# VF_4Channel_ResistanceMixer.net
KiCad netlist of a schematic drawn in EAGLE
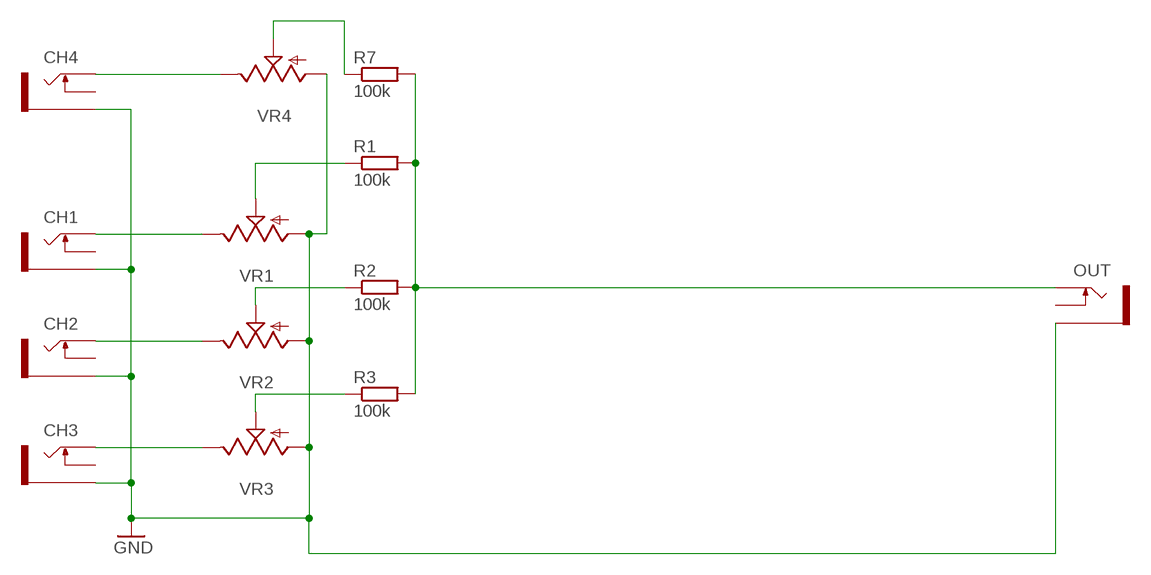
[diagram p0: schematic, sheet 1]

(export (version "E")
  (design (tool "Eeschema 10.0.6"))
  (components
    (comp (ref "CH1")
      (value "THONKICONNNEW")
      (footprint "eagle-import:WQP-PJ301M-12_JACK")
      (libsource (lib "eagle-import") (part "THONKICONNNEW"))
    )
    (comp (ref "CH2")
      (value "THONKICONNNEW")
      (footprint "eagle-import:WQP-PJ301M-12_JACK")
      (libsource (lib "eagle-import") (part "THONKICONNNEW"))
    )
    (comp (ref "CH3")
      (value "THONKICONNNEW")
      (footprint "eagle-import:WQP-PJ301M-12_JACK")
      (libsource (lib "eagle-import") (part "THONKICONNNEW"))
    )
    (comp (ref "CH4")
      (value "THONKICONNNEW")
      (footprint "eagle-import:WQP-PJ301M-12_JACK")
      (libsource (lib "eagle-import") (part "THONKICONNNEW"))
    )
    (comp (ref "OUT")
      (value "THONKICONNNEW")
      (footprint "eagle-import:WQP-PJ301M-12_JACK")
      (libsource (lib "eagle-import") (part "THONKICONNNEW"))
    )
    (comp (ref "R1")
      (value "100k")
      (footprint "eagle-import:7MM_RESISTOR")
      (libsource (lib "eagle-import") (part "RESISTOR7MM"))
    )
    (comp (ref "R2")
      (value "100k")
      (footprint "eagle-import:7MM_RESISTOR")
      (libsource (lib "eagle-import") (part "RESISTOR7MM"))
    )
    (comp (ref "R3")
      (value "100k")
      (footprint "eagle-import:7MM_RESISTOR")
      (libsource (lib "eagle-import") (part "RESISTOR7MM"))
    )
    (comp (ref "R7")
      (value "100k")
      (footprint "eagle-import:7MM_RESISTOR")
      (libsource (lib "eagle-import") (part "RESISTOR7MM"))
    )
    (comp (ref "VR1")
      (value "9MM_SNAP-IN_POT_")
      (footprint "eagle-import:9MM_SNAP-IN_POT")
      (libsource (lib "eagle-import") (part "9MM_SNAP-IN_POT_"))
    )
    (comp (ref "VR2")
      (value "9MM_SNAP-IN_POT_")
      (footprint "eagle-import:9MM_SNAP-IN_POT")
      (libsource (lib "eagle-import") (part "9MM_SNAP-IN_POT_"))
    )
    (comp (ref "VR3")
      (value "9MM_SNAP-IN_POT_")
      (footprint "eagle-import:9MM_SNAP-IN_POT")
      (libsource (lib "eagle-import") (part "9MM_SNAP-IN_POT_"))
    )
    (comp (ref "VR4")
      (value "9MM_SNAP-IN_POT_")
      (footprint "eagle-import:9MM_SNAP-IN_POT")
      (libsource (lib "eagle-import") (part "9MM_SNAP-IN_POT_"))
    )
  )
  (nets
    (net (code "1") (name "GND") (class "Default")
      (node (ref "CH1") (pin "P$3_SLEEVE") (pinfunction "SLEEVE_P$3_SLEEVE") (pintype "passive"))
      (node (ref "CH2") (pin "P$3_SLEEVE") (pinfunction "SLEEVE_P$3_SLEEVE") (pintype "passive"))
      (node (ref "CH3") (pin "P$3_SLEEVE") (pinfunction "SLEEVE_P$3_SLEEVE") (pintype "passive"))
      (node (ref "CH4") (pin "P$3_SLEEVE") (pinfunction "SLEEVE_P$3_SLEEVE") (pintype "passive"))
      (node (ref "OUT") (pin "P$3_SLEEVE") (pinfunction "SLEEVE_P$3_SLEEVE") (pintype "passive"))
      (node (ref "VR1") (pin "1") (pinfunction "A_1") (pintype "passive"))
      (node (ref "VR2") (pin "1") (pinfunction "A_1") (pintype "passive"))
      (node (ref "VR3") (pin "1") (pinfunction "A_1") (pintype "passive"))
      (node (ref "VR4") (pin "1") (pinfunction "A_1") (pintype "passive"))
    )
    (net (code "2") (name "Net-(CH1-TIP)") (class "Default")
      (node (ref "CH1") (pin "P$1_TIP") (pinfunction "TIP_P$1_TIP") (pintype "passive"))
      (node (ref "VR1") (pin "3") (pinfunction "E_3") (pintype "passive"))
    )
    (net (code "3") (name "Net-(CH2-TIP)") (class "Default")
      (node (ref "CH2") (pin "P$1_TIP") (pinfunction "TIP_P$1_TIP") (pintype "passive"))
      (node (ref "VR2") (pin "3") (pinfunction "E_3") (pintype "passive"))
    )
    (net (code "4") (name "Net-(CH3-TIP)") (class "Default")
      (node (ref "CH3") (pin "P$1_TIP") (pinfunction "TIP_P$1_TIP") (pintype "passive"))
      (node (ref "VR3") (pin "3") (pinfunction "E_3") (pintype "passive"))
    )
    (net (code "5") (name "Net-(CH4-TIP)") (class "Default")
      (node (ref "CH4") (pin "P$1_TIP") (pinfunction "TIP_P$1_TIP") (pintype "passive"))
      (node (ref "VR4") (pin "3") (pinfunction "E_3") (pintype "passive"))
    )
    (net (code "6") (name "Net-(OUT-TIP)") (class "Default")
      (node (ref "OUT") (pin "P$1_TIP") (pinfunction "TIP_P$1_TIP") (pintype "passive"))
      (node (ref "R1") (pin "2") (pinfunction "2_2") (pintype "passive"))
      (node (ref "R2") (pin "2") (pinfunction "2_2") (pintype "passive"))
      (node (ref "R3") (pin "2") (pinfunction "2_2") (pintype "passive"))
      (node (ref "R7") (pin "2") (pinfunction "2_2") (pintype "passive"))
    )
    (net (code "7") (name "Net-(VR1-S)") (class "Default")
      (node (ref "R1") (pin "1") (pinfunction "1_1") (pintype "passive"))
      (node (ref "VR1") (pin "2") (pinfunction "S_2") (pintype "passive"))
    )
    (net (code "8") (name "Net-(VR2-S)") (class "Default")
      (node (ref "R2") (pin "1") (pinfunction "1_1") (pintype "passive"))
      (node (ref "VR2") (pin "2") (pinfunction "S_2") (pintype "passive"))
    )
    (net (code "9") (name "Net-(VR3-S)") (class "Default")
      (node (ref "R3") (pin "1") (pinfunction "1_1") (pintype "passive"))
      (node (ref "VR3") (pin "2") (pinfunction "S_2") (pintype "passive"))
    )
    (net (code "10") (name "Net-(VR4-S)") (class "Default")
      (node (ref "R7") (pin "1") (pinfunction "1_1") (pintype "passive"))
      (node (ref "VR4") (pin "2") (pinfunction "S_2") (pintype "passive"))
    )
    (net (code "11") (name "unconnected-(CH1-SWITCH-PadP$2_SWITCH)") (class "Default")
      (node (ref "CH1") (pin "P$2_SWITCH") (pinfunction "SWITCH_P$2_SWITCH") (pintype "passive"))
    )
    (net (code "12") (name "unconnected-(CH2-SWITCH-PadP$2_SWITCH)") (class "Default")
      (node (ref "CH2") (pin "P$2_SWITCH") (pinfunction "SWITCH_P$2_SWITCH") (pintype "passive"))
    )
    (net (code "13") (name "unconnected-(CH3-SWITCH-PadP$2_SWITCH)") (class "Default")
      (node (ref "CH3") (pin "P$2_SWITCH") (pinfunction "SWITCH_P$2_SWITCH") (pintype "passive"))
    )
    (net (code "14") (name "unconnected-(CH4-SWITCH-PadP$2_SWITCH)") (class "Default")
      (node (ref "CH4") (pin "P$2_SWITCH") (pinfunction "SWITCH_P$2_SWITCH") (pintype "passive"))
    )
    (net (code "15") (name "unconnected-(OUT-SWITCH-PadP$2_SWITCH)") (class "Default")
      (node (ref "OUT") (pin "P$2_SWITCH") (pinfunction "SWITCH_P$2_SWITCH") (pintype "passive"))
    )
  )
)
